# LAB03-1_2020-11-16_17-30-34.net
KiCad netlist of a schematic drawn in EasyEDA
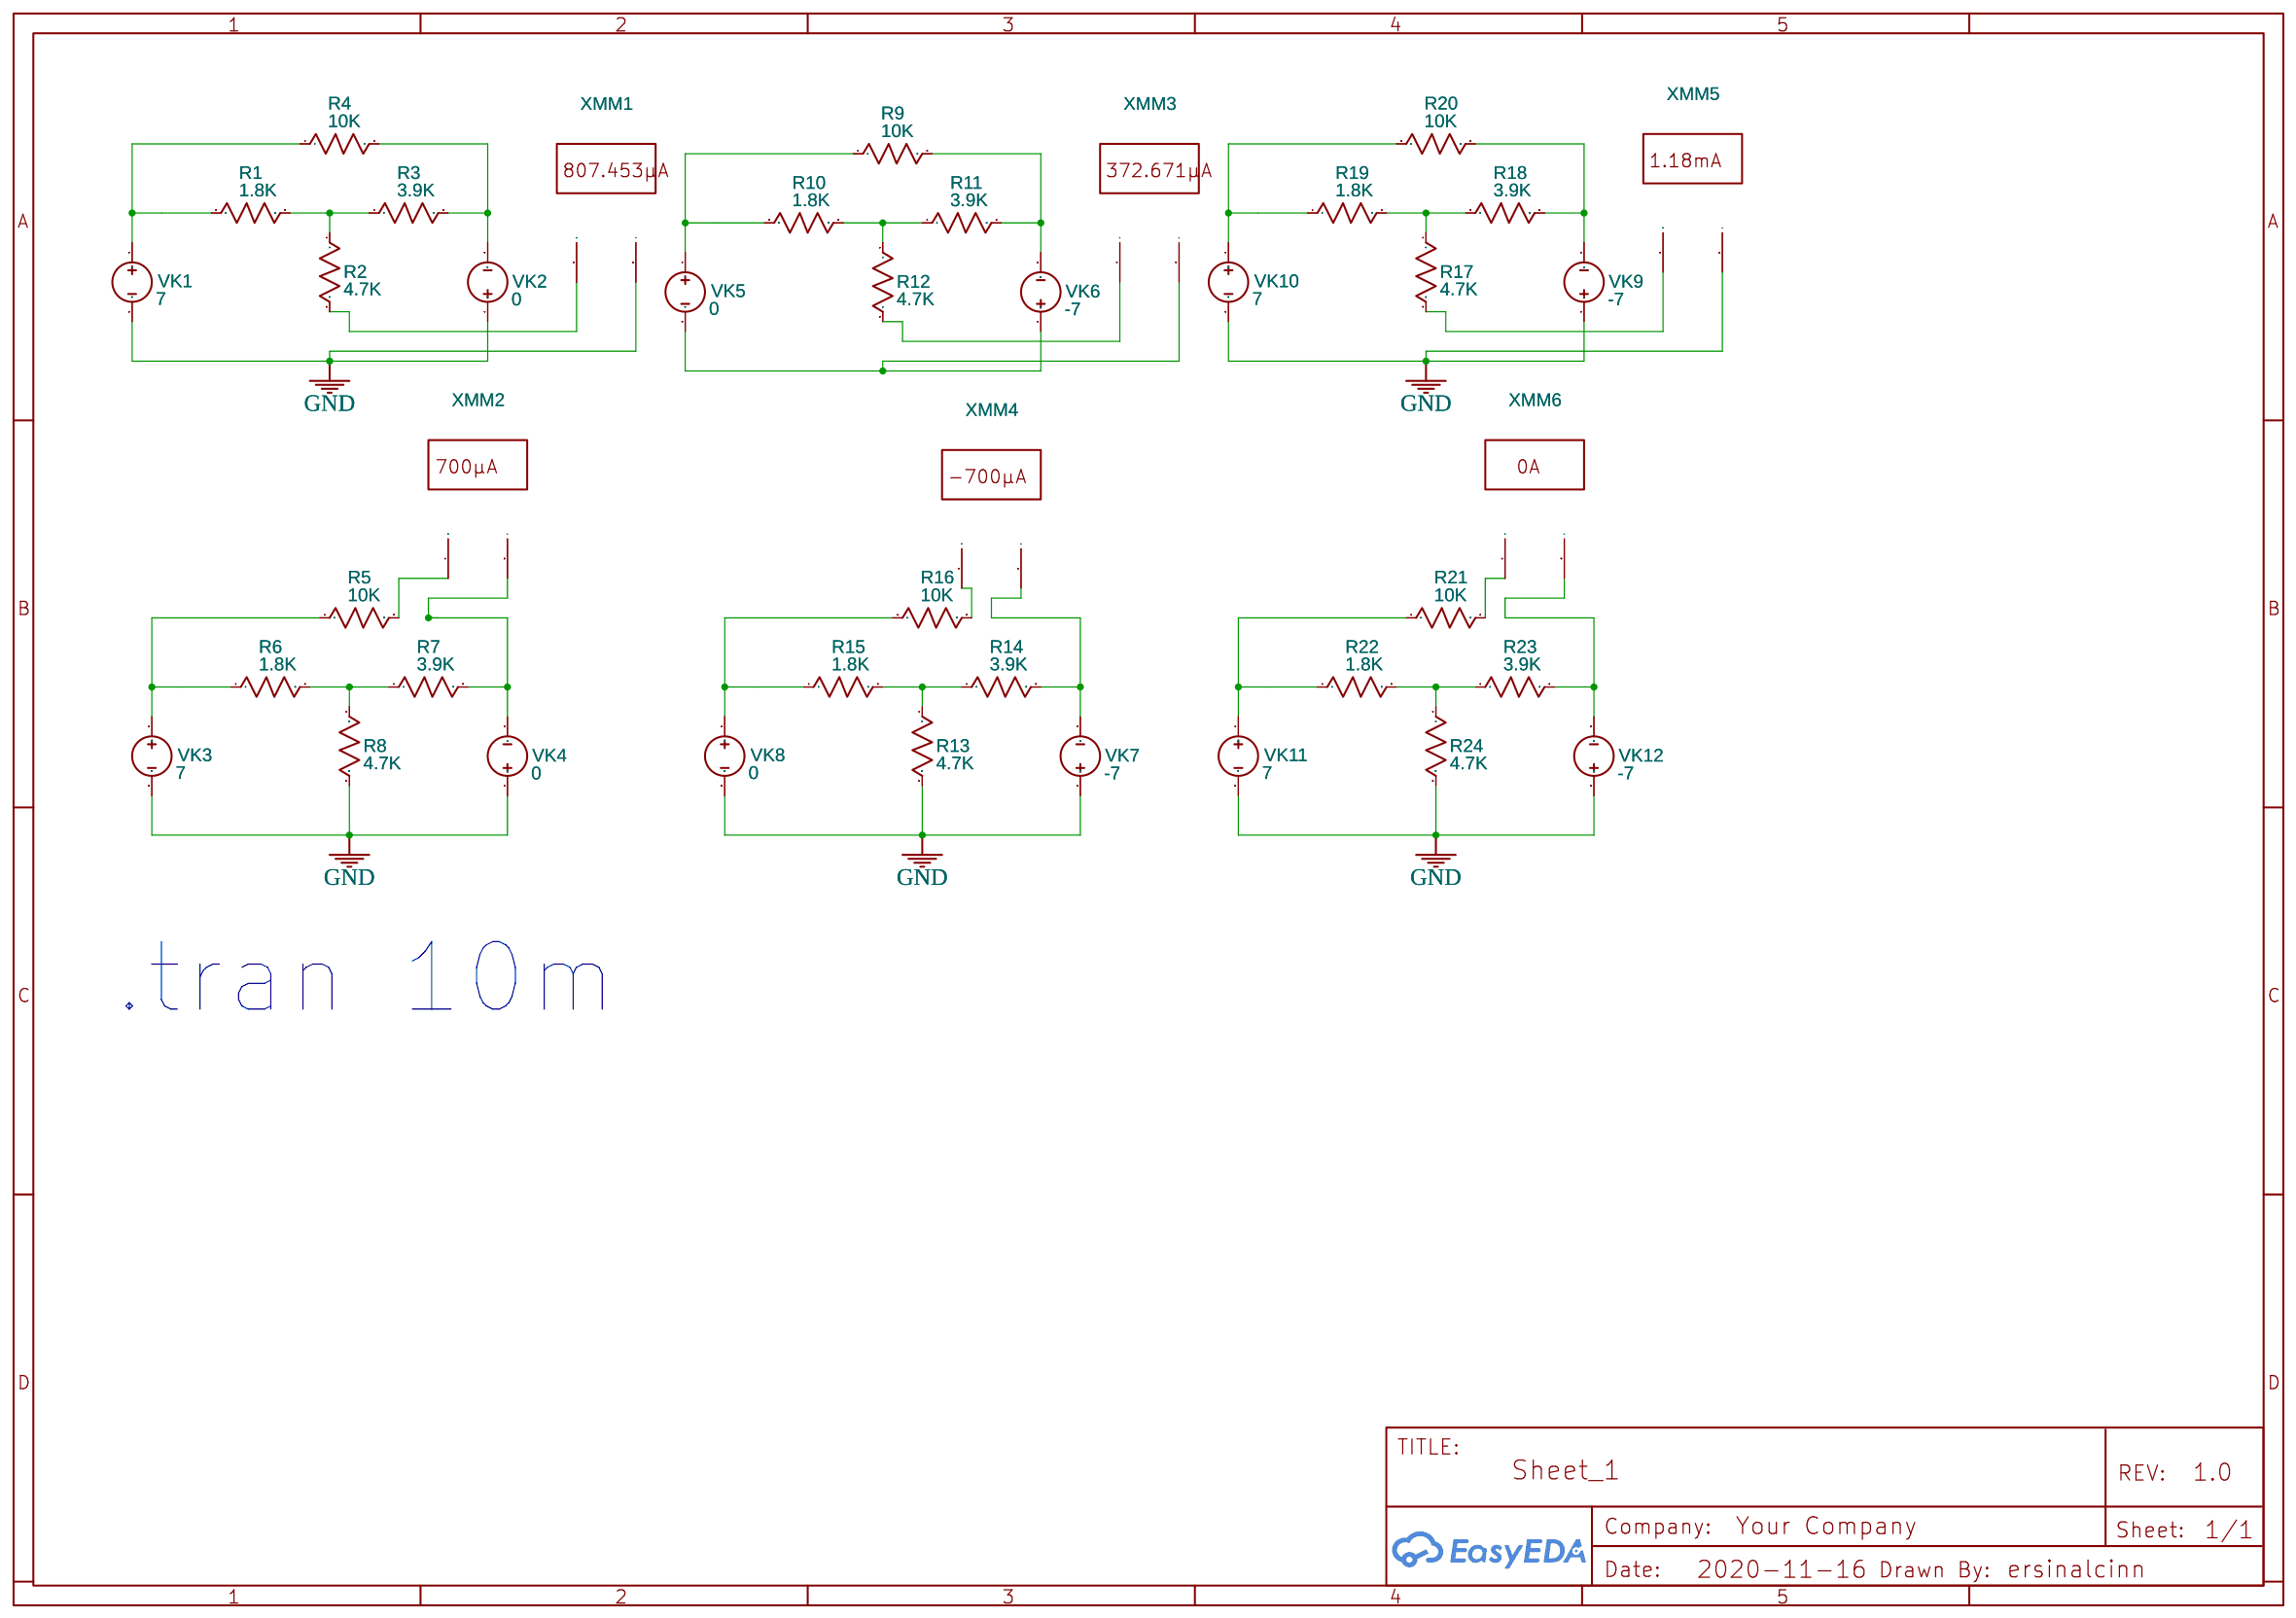
[diagram p0: schematic sheet]

(export (version "E")
  (design (tool "Eeschema 10.0.6"))
  (components
    (comp (ref "R1") (value "1.8K") (libsource (lib "") (part "Resistor_US")))
    (comp (ref "R2") (value "4.7K") (libsource (lib "") (part "Resistor_US_1")))
    (comp (ref "R3") (value "3.9K") (libsource (lib "") (part "Resistor_US")))
    (comp (ref "R4") (value "10K") (libsource (lib "") (part "Resistor_US")))
    (comp (ref "R5") (value "10K") (libsource (lib "") (part "Resistor_US")))
    (comp (ref "R6") (value "1.8K") (libsource (lib "") (part "Resistor_US")))
    (comp (ref "R7") (value "3.9K") (libsource (lib "") (part "Resistor_US")))
    (comp (ref "R8") (value "4.7K") (libsource (lib "") (part "Resistor_US_1")))
    (comp (ref "R9") (value "10K") (libsource (lib "") (part "Resistor_US")))
    (comp (ref "R10") (value "1.8K") (libsource (lib "") (part "Resistor_US")))
    (comp (ref "R11") (value "3.9K") (libsource (lib "") (part "Resistor_US")))
    (comp (ref "R12") (value "4.7K") (libsource (lib "") (part "Resistor_US_1")))
    (comp (ref "R13") (value "4.7K") (libsource (lib "") (part "Resistor_US_1")))
    (comp (ref "R14") (value "3.9K") (libsource (lib "") (part "Resistor_US")))
    (comp (ref "R15") (value "1.8K") (libsource (lib "") (part "Resistor_US")))
    (comp (ref "R16") (value "10K") (libsource (lib "") (part "Resistor_US")))
    (comp (ref "R17") (value "4.7K") (libsource (lib "") (part "Resistor_US_1")))
    (comp (ref "R18") (value "3.9K") (libsource (lib "") (part "Resistor_US")))
    (comp (ref "R19") (value "1.8K") (libsource (lib "") (part "Resistor_US")))
    (comp (ref "R20") (value "10K") (libsource (lib "") (part "Resistor_US")))
    (comp (ref "R21") (value "10K") (libsource (lib "") (part "Resistor_US")))
    (comp (ref "R22") (value "1.8K") (libsource (lib "") (part "Resistor_US")))
    (comp (ref "R23") (value "3.9K") (libsource (lib "") (part "Resistor_US")))
    (comp (ref "R24") (value "4.7K") (libsource (lib "") (part "Resistor_US_1")))
    (comp (ref "VK1") (value "7") (libsource (lib "") (part "VDC")))
    (comp (ref "VK2") (value "0") (libsource (lib "") (part "VDC_1")))
    (comp (ref "VK3") (value "7") (libsource (lib "") (part "VDC")))
    (comp (ref "VK4") (value "0") (libsource (lib "") (part "VDC_1")))
    (comp (ref "VK5") (value "0") (libsource (lib "") (part "VDC")))
    (comp (ref "VK6") (value "-7") (libsource (lib "") (part "VDC_1")))
    (comp (ref "VK7") (value "-7") (libsource (lib "") (part "VDC_1")))
    (comp (ref "VK8") (value "0") (libsource (lib "") (part "VDC")))
    (comp (ref "VK9") (value "-7") (libsource (lib "") (part "VDC_1")))
    (comp (ref "VK10") (value "7") (libsource (lib "") (part "VDC")))
    (comp (ref "VK11") (value "7") (libsource (lib "") (part "VDC")))
    (comp (ref "VK12") (value "-7") (libsource (lib "") (part "VDC_1")))
    (comp (ref "XMM1") (value "Multimeter") (libsource (lib "") (part "MULTIMETER_4")))
    (comp (ref "XMM2") (value "Multimeter") (libsource (lib "") (part "MULTIMETER_1")))
    (comp (ref "XMM3") (value "Multimeter") (libsource (lib "") (part "MULTIMETER_2")))
    (comp (ref "XMM4") (value "Multimeter") (libsource (lib "") (part "MULTIMETER_3")))
    (comp (ref "XMM5") (value "Multimeter") (libsource (lib "") (part "MULTIMETER")))
    (comp (ref "XMM6") (value "Multimeter") (libsource (lib "") (part "MULTIMETER_5")))
  )
  (nets
    (net (code "1") (name "GND") (class "Default")
      (node (ref "R13") (pin "2") (pinfunction "2_2") (pintype "unspecified"))
      (node (ref "R24") (pin "2") (pinfunction "2_2") (pintype "unspecified"))
      (node (ref "R8") (pin "2") (pinfunction "2_2") (pintype "unspecified"))
      (node (ref "VK1") (pin "2") (pinfunction "2_2") (pintype "unspecified"))
      (node (ref "VK10") (pin "2") (pinfunction "2_2") (pintype "unspecified"))
      (node (ref "VK11") (pin "2") (pinfunction "2_2") (pintype "unspecified"))
      (node (ref "VK12") (pin "1") (pinfunction "1_1") (pintype "unspecified"))
      (node (ref "VK2") (pin "1") (pinfunction "1_1") (pintype "unspecified"))
      (node (ref "VK3") (pin "2") (pinfunction "2_2") (pintype "unspecified"))
      (node (ref "VK4") (pin "1") (pinfunction "1_1") (pintype "unspecified"))
      (node (ref "VK7") (pin "1") (pinfunction "1_1") (pintype "unspecified"))
      (node (ref "VK8") (pin "2") (pinfunction "2_2") (pintype "unspecified"))
      (node (ref "VK9") (pin "1") (pinfunction "1_1") (pintype "unspecified"))
      (node (ref "XMM1") (pin "2") (pinfunction "I_2") (pintype "unspecified"))
      (node (ref "XMM5") (pin "2") (pinfunction "I_2") (pintype "unspecified"))
    )
    (net (code "2") (name "Net-(R1-Pad1)") (class "Default")
      (node (ref "R1") (pin "1") (pinfunction "1_1") (pintype "unspecified"))
      (node (ref "R4") (pin "1") (pinfunction "1_1") (pintype "unspecified"))
      (node (ref "VK1") (pin "1") (pinfunction "1_1") (pintype "unspecified"))
    )
    (net (code "3") (name "Net-(R1-Pad2)") (class "Default")
      (node (ref "R1") (pin "2") (pinfunction "2_2") (pintype "unspecified"))
      (node (ref "R2") (pin "1") (pinfunction "1_1") (pintype "unspecified"))
      (node (ref "R3") (pin "1") (pinfunction "1_1") (pintype "unspecified"))
    )
    (net (code "4") (name "Net-(R3-Pad2)") (class "Default")
      (node (ref "R3") (pin "2") (pinfunction "2_2") (pintype "unspecified"))
      (node (ref "R4") (pin "2") (pinfunction "2_2") (pintype "unspecified"))
      (node (ref "VK2") (pin "2") (pinfunction "2_2") (pintype "unspecified"))
    )
    (net (code "5") (name "Net-(R5-Pad1)") (class "Default")
      (node (ref "R5") (pin "1") (pinfunction "1_1") (pintype "unspecified"))
      (node (ref "R6") (pin "1") (pinfunction "1_1") (pintype "unspecified"))
      (node (ref "VK3") (pin "1") (pinfunction "1_1") (pintype "unspecified"))
    )
    (net (code "6") (name "Net-(R6-Pad2)") (class "Default")
      (node (ref "R6") (pin "2") (pinfunction "2_2") (pintype "unspecified"))
      (node (ref "R7") (pin "1") (pinfunction "1_1") (pintype "unspecified"))
      (node (ref "R8") (pin "1") (pinfunction "1_1") (pintype "unspecified"))
    )
    (net (code "7") (name "Net-(R10-Pad1)") (class "Default")
      (node (ref "R10") (pin "1") (pinfunction "1_1") (pintype "unspecified"))
      (node (ref "R9") (pin "1") (pinfunction "1_1") (pintype "unspecified"))
      (node (ref "VK5") (pin "1") (pinfunction "1_1") (pintype "unspecified"))
    )
    (net (code "8") (name "Net-(R10-Pad2)") (class "Default")
      (node (ref "R10") (pin "2") (pinfunction "2_2") (pintype "unspecified"))
      (node (ref "R11") (pin "1") (pinfunction "1_1") (pintype "unspecified"))
      (node (ref "R12") (pin "1") (pinfunction "1_1") (pintype "unspecified"))
    )
    (net (code "9") (name "Net-(R11-Pad2)") (class "Default")
      (node (ref "R11") (pin "2") (pinfunction "2_2") (pintype "unspecified"))
      (node (ref "R9") (pin "2") (pinfunction "2_2") (pintype "unspecified"))
      (node (ref "VK6") (pin "2") (pinfunction "2_2") (pintype "unspecified"))
    )
    (net (code "10") (name "Net-(R13-Pad1)") (class "Default")
      (node (ref "R13") (pin "1") (pinfunction "1_1") (pintype "unspecified"))
      (node (ref "R14") (pin "1") (pinfunction "1_1") (pintype "unspecified"))
      (node (ref "R15") (pin "2") (pinfunction "2_2") (pintype "unspecified"))
    )
    (net (code "11") (name "Net-(R15-Pad1)") (class "Default")
      (node (ref "R15") (pin "1") (pinfunction "1_1") (pintype "unspecified"))
      (node (ref "R16") (pin "1") (pinfunction "1_1") (pintype "unspecified"))
      (node (ref "VK8") (pin "1") (pinfunction "1_1") (pintype "unspecified"))
    )
    (net (code "12") (name "Net-(R17-Pad1)") (class "Default")
      (node (ref "R17") (pin "1") (pinfunction "1_1") (pintype "unspecified"))
      (node (ref "R18") (pin "1") (pinfunction "1_1") (pintype "unspecified"))
      (node (ref "R19") (pin "2") (pinfunction "2_2") (pintype "unspecified"))
    )
    (net (code "13") (name "Net-(R18-Pad2)") (class "Default")
      (node (ref "R18") (pin "2") (pinfunction "2_2") (pintype "unspecified"))
      (node (ref "R20") (pin "2") (pinfunction "2_2") (pintype "unspecified"))
      (node (ref "VK9") (pin "2") (pinfunction "2_2") (pintype "unspecified"))
    )
    (net (code "14") (name "Net-(R19-Pad1)") (class "Default")
      (node (ref "R19") (pin "1") (pinfunction "1_1") (pintype "unspecified"))
      (node (ref "R20") (pin "1") (pinfunction "1_1") (pintype "unspecified"))
      (node (ref "VK10") (pin "1") (pinfunction "1_1") (pintype "unspecified"))
    )
    (net (code "15") (name "Net-(R21-Pad1)") (class "Default")
      (node (ref "R21") (pin "1") (pinfunction "1_1") (pintype "unspecified"))
      (node (ref "R22") (pin "1") (pinfunction "1_1") (pintype "unspecified"))
      (node (ref "VK11") (pin "1") (pinfunction "1_1") (pintype "unspecified"))
    )
    (net (code "16") (name "Net-(R22-Pad2)") (class "Default")
      (node (ref "R22") (pin "2") (pinfunction "2_2") (pintype "unspecified"))
      (node (ref "R23") (pin "1") (pinfunction "1_1") (pintype "unspecified"))
      (node (ref "R24") (pin "1") (pinfunction "1_1") (pintype "unspecified"))
    )
    (net (code "17") (name "Net-(XMM1-+)") (class "Default")
      (node (ref "R2") (pin "2") (pinfunction "2_2") (pintype "unspecified"))
      (node (ref "XMM1") (pin "1") (pinfunction "+_1") (pintype "unspecified"))
    )
    (net (code "18") (name "Net-(XMM2-+)") (class "Default")
      (node (ref "R5") (pin "2") (pinfunction "2_2") (pintype "unspecified"))
      (node (ref "XMM2") (pin "1") (pinfunction "+_1") (pintype "unspecified"))
    )
    (net (code "19") (name "Net-(XMM2-I)") (class "Default")
      (node (ref "R7") (pin "2") (pinfunction "2_2") (pintype "unspecified"))
      (node (ref "VK4") (pin "2") (pinfunction "2_2") (pintype "unspecified"))
      (node (ref "XMM2") (pin "2") (pinfunction "I_2") (pintype "unspecified"))
    )
    (net (code "20") (name "Net-(XMM3-+)") (class "Default")
      (node (ref "R12") (pin "2") (pinfunction "2_2") (pintype "unspecified"))
      (node (ref "XMM3") (pin "1") (pinfunction "+_1") (pintype "unspecified"))
    )
    (net (code "21") (name "Net-(XMM3-I)") (class "Default")
      (node (ref "VK5") (pin "2") (pinfunction "2_2") (pintype "unspecified"))
      (node (ref "VK6") (pin "1") (pinfunction "1_1") (pintype "unspecified"))
      (node (ref "XMM3") (pin "2") (pinfunction "I_2") (pintype "unspecified"))
    )
    (net (code "22") (name "Net-(XMM4-+)") (class "Default")
      (node (ref "R16") (pin "2") (pinfunction "2_2") (pintype "unspecified"))
      (node (ref "XMM4") (pin "1") (pinfunction "+_1") (pintype "unspecified"))
    )
    (net (code "23") (name "Net-(XMM4-I)") (class "Default")
      (node (ref "R14") (pin "2") (pinfunction "2_2") (pintype "unspecified"))
      (node (ref "VK7") (pin "2") (pinfunction "2_2") (pintype "unspecified"))
      (node (ref "XMM4") (pin "2") (pinfunction "I_2") (pintype "unspecified"))
    )
    (net (code "24") (name "Net-(XMM5-+)") (class "Default")
      (node (ref "R17") (pin "2") (pinfunction "2_2") (pintype "unspecified"))
      (node (ref "XMM5") (pin "1") (pinfunction "+_1") (pintype "unspecified"))
    )
    (net (code "25") (name "Net-(XMM6-+)") (class "Default")
      (node (ref "R21") (pin "2") (pinfunction "2_2") (pintype "unspecified"))
      (node (ref "XMM6") (pin "1") (pinfunction "+_1") (pintype "unspecified"))
    )
    (net (code "26") (name "Net-(XMM6-I)") (class "Default")
      (node (ref "R23") (pin "2") (pinfunction "2_2") (pintype "unspecified"))
      (node (ref "VK12") (pin "2") (pinfunction "2_2") (pintype "unspecified"))
      (node (ref "XMM6") (pin "2") (pinfunction "I_2") (pintype "unspecified"))
    )
  )
)
